# BHONoff.net
KiCad netlist of a schematic drawn in EAGLE
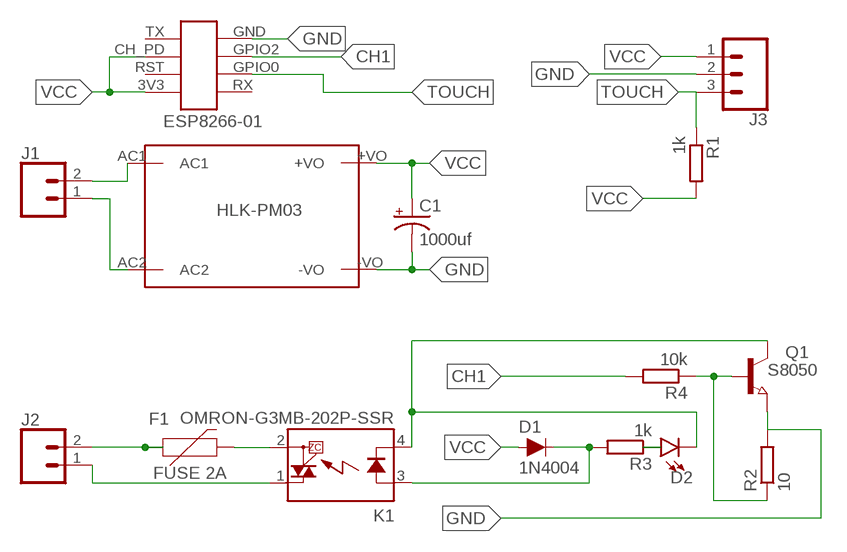
[diagram p0: schematic, sheet 1]

(export (version "E")
  (design (tool "Eeschema 10.0.6"))
  (components
    (comp (ref "C1")
      (value "1000uf")
      (footprint "eagle-import:140CLH-1010")
      (libsource (lib "eagle-import") (part "CPOL-US140CLH-1010"))
    )
    (comp (ref "D1")
      (value "1N4004")
      (footprint "eagle-import:SOD-323")
      (libsource (lib "eagle-import") (part "DIODE-BAS16J"))
    )
    (comp (ref "D2")
      (value "LED0603")
      (footprint "eagle-import:LED-0603")
      (libsource (lib "eagle-import") (part "LED0603"))
    )
    (comp (ref "F1")
      (value "FUSE 2A")
      (footprint "eagle-import:PTH")
      (libsource (lib "eagle-import") (part "PPTC_PTH"))
    )
    (comp (ref "J1")
      (value "CONN_025MM")
      (footprint "eagle-import:SCREWTERMINAL-5MM-2")
      (libsource (lib "eagle-import") (part "CONN_025MM"))
    )
    (comp (ref "J2")
      (value "CONN_025MM")
      (footprint "eagle-import:SCREWTERMINAL-5MM-2")
      (libsource (lib "eagle-import") (part "CONN_025MM"))
    )
    (comp (ref "J3")
      (value "CONN_03")
      (footprint "eagle-import:1X03")
      (libsource (lib "eagle-import") (part "CONN_03"))
    )
    (comp (ref "K1")
      (value "OMRON-G3MB-202P-SSR")
      (footprint "eagle-import:OMRON-G3MB-202P-SSR")
      (libsource (lib "eagle-import") (part "OMRON-G3MB-202P-SSR"))
    )
    (comp (ref "Q1")
      (value "S8050")
      (footprint "eagle-import:SOT23")
      (libsource (lib "eagle-import") (part "NPN-TRANSISTOR_SOT23"))
    )
    (comp (ref "R1")
      (value "1k")
      (footprint "eagle-import:R0603")
      (libsource (lib "eagle-import") (part "R-EU_R0603"))
    )
    (comp (ref "R2")
      (value "10")
      (footprint "eagle-import:R0603")
      (libsource (lib "eagle-import") (part "R-EU_R0603"))
    )
    (comp (ref "R3")
      (value "1k")
      (footprint "eagle-import:R0603")
      (libsource (lib "eagle-import") (part "R-EU_R0603"))
    )
    (comp (ref "R4")
      (value "10k")
      (footprint "eagle-import:R0603")
      (libsource (lib "eagle-import") (part "R-EU_R0603"))
    )
    (comp (ref "U$2")
      (value "HLK-PM03")
      (footprint "eagle-import:HLK-PM03")
      (libsource (lib "eagle-import") (part "HLK-PM03"))
    )
    (comp (ref "U$3")
      (value "ESP8266-01")
      (footprint "eagle-import:ESP8266-01")
      (libsource (lib "eagle-import") (part "ESP8266-01"))
    )
  )
  (nets
    (net (code "1") (name "CH1") (class "Default")
      (node (ref "R4") (pin "2") (pinfunction "2_2") (pintype "passive"))
      (node (ref "U$3") (pin "GPIO2") (pinfunction "GPIO2_GPIO2") (pintype "bidirectional"))
    )
    (net (code "2") (name "GND") (class "Default")
      (node (ref "C1") (pin "-") (pinfunction "-_-") (pintype "passive"))
      (node (ref "J3") (pin "2") (pinfunction "2_2") (pintype "passive"))
      (node (ref "Q1") (pin "2") (pinfunction "E_2") (pintype "passive"))
      (node (ref "R2") (pin "2") (pinfunction "2_2") (pintype "passive"))
      (node (ref "U$2") (pin "-VO") (pinfunction "-VO_-VO") (pintype "bidirectional"))
      (node (ref "U$3") (pin "GND") (pinfunction "GND_GND") (pintype "bidirectional"))
    )
    (net (code "3") (name "Net-(D2-PadA)") (class "Default")
      (node (ref "D2") (pin "A") (pinfunction "A_A") (pintype "passive"))
      (node (ref "R3") (pin "1") (pinfunction "1_1") (pintype "passive"))
    )
    (net (code "4") (name "Net-(F1-1)") (class "Default")
      (node (ref "F1") (pin "P$1") (pinfunction "1_P$1") (pintype "bidirectional"))
      (node (ref "J2") (pin "2") (pinfunction "2_2") (pintype "passive"))
    )
    (net (code "5") (name "Net-(F1-2)") (class "Default")
      (node (ref "F1") (pin "P$2") (pinfunction "2_P$2") (pintype "bidirectional"))
      (node (ref "K1") (pin "2") (pinfunction "DS2_2") (pintype "passive"))
    )
    (net (code "6") (name "Net-(J1-Pad1)") (class "Default")
      (node (ref "J1") (pin "1") (pinfunction "1_1") (pintype "passive"))
      (node (ref "U$2") (pin "AC2") (pinfunction "AC2_AC2") (pintype "bidirectional"))
    )
    (net (code "7") (name "Net-(J1-Pad2)") (class "Default")
      (node (ref "J1") (pin "2") (pinfunction "2_2") (pintype "passive"))
      (node (ref "U$2") (pin "AC1") (pinfunction "AC1_AC1") (pintype "bidirectional"))
    )
    (net (code "8") (name "Net-(K1-A)") (class "Default")
      (node (ref "D1") (pin "C") (pinfunction "C_C") (pintype "passive"))
      (node (ref "K1") (pin "3") (pinfunction "A_3") (pintype "passive"))
      (node (ref "R3") (pin "2") (pinfunction "2_2") (pintype "passive"))
    )
    (net (code "9") (name "Net-(K1-DS1)") (class "Default")
      (node (ref "J2") (pin "1") (pinfunction "1_1") (pintype "passive"))
      (node (ref "K1") (pin "1") (pinfunction "DS1_1") (pintype "passive"))
    )
    (net (code "10") (name "Net-(K1-K)") (class "Default")
      (node (ref "D2") (pin "C") (pinfunction "C_C") (pintype "passive"))
      (node (ref "K1") (pin "4") (pinfunction "K_4") (pintype "passive"))
      (node (ref "Q1") (pin "3") (pinfunction "C_3") (pintype "passive"))
    )
    (net (code "11") (name "Net-(Q1-B)") (class "Default")
      (node (ref "Q1") (pin "1") (pinfunction "B_1") (pintype "passive"))
      (node (ref "R2") (pin "1") (pinfunction "1_1") (pintype "passive"))
      (node (ref "R4") (pin "1") (pinfunction "1_1") (pintype "passive"))
    )
    (net (code "12") (name "TOUCH") (class "Default")
      (node (ref "J3") (pin "3") (pinfunction "3_3") (pintype "passive"))
      (node (ref "R1") (pin "1") (pinfunction "1_1") (pintype "passive"))
      (node (ref "U$3") (pin "GPIO0") (pinfunction "GPIO0_GPIO0") (pintype "bidirectional"))
    )
    (net (code "13") (name "VCC") (class "Default")
      (node (ref "C1") (pin "+") (pinfunction "+_+") (pintype "passive"))
      (node (ref "D1") (pin "A") (pinfunction "A_A") (pintype "passive"))
      (node (ref "J3") (pin "1") (pinfunction "1_1") (pintype "passive"))
      (node (ref "R1") (pin "2") (pinfunction "2_2") (pintype "passive"))
      (node (ref "U$2") (pin "+VO") (pinfunction "+VO_+VO") (pintype "bidirectional"))
      (node (ref "U$3") (pin "3V3") (pinfunction "3V3_3V3") (pintype "bidirectional"))
      (node (ref "U$3") (pin "CH_PD") (pinfunction "CH_PD_CH_PD") (pintype "bidirectional"))
    )
    (net (code "14") (name "unconnected-(U$3-PadRST)") (class "Default")
      (node (ref "U$3") (pin "RST") (pinfunction "RST_RST") (pintype "bidirectional"))
    )
    (net (code "15") (name "unconnected-(U$3-PadRX)") (class "Default")
      (node (ref "U$3") (pin "RX") (pinfunction "RX_RX") (pintype "bidirectional"))
    )
    (net (code "16") (name "unconnected-(U$3-PadTX)") (class "Default")
      (node (ref "U$3") (pin "TX") (pinfunction "TX_TX") (pintype "bidirectional"))
    )
  )
)
